# SENSOR_GARIS.net
KiCad netlist of a schematic drawn in EAGLE
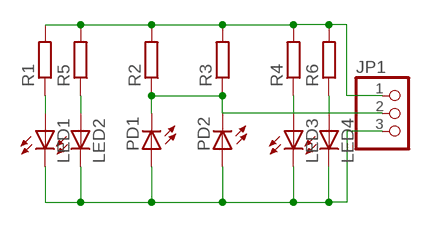
[diagram p0: schematic, sheet 1]

(export (version "E")
  (design (tool "Eeschema 10.0.6"))
  (components
    (comp (ref "JP1")
      (value "PINHD-1X3")
      (footprint "eagle-import:1X03")
      (libsource (lib "eagle-import") (part "PINHD-1X3"))
    )
    (comp (ref "LED1")
      (value "LED3MM")
      (footprint "eagle-import:LED3MM")
      (libsource (lib "eagle-import") (part "LED3MM"))
    )
    (comp (ref "LED2")
      (value "LED3MM")
      (footprint "eagle-import:LED3MM")
      (libsource (lib "eagle-import") (part "LED3MM"))
    )
    (comp (ref "LED3")
      (value "LED3MM")
      (footprint "eagle-import:LED3MM")
      (libsource (lib "eagle-import") (part "LED3MM"))
    )
    (comp (ref "LED4")
      (value "LED3MM")
      (footprint "eagle-import:LED3MM")
      (libsource (lib "eagle-import") (part "LED3MM"))
    )
    (comp (ref "PD1")
      (value "LED3MM")
      (footprint "eagle-import:LED3MM")
      (libsource (lib "eagle-import") (part "LED3MM"))
    )
    (comp (ref "PD2")
      (value "LED3MM")
      (footprint "eagle-import:LED3MM")
      (libsource (lib "eagle-import") (part "LED3MM"))
    )
    (comp (ref "R1")
      (value "R-EU_M0805")
      (footprint "eagle-import:M0805")
      (libsource (lib "eagle-import") (part "R-EU_M0805"))
    )
    (comp (ref "R2")
      (value "R-EU_M0805")
      (footprint "eagle-import:M0805")
      (libsource (lib "eagle-import") (part "R-EU_M0805"))
    )
    (comp (ref "R3")
      (value "R-EU_M0805")
      (footprint "eagle-import:M0805")
      (libsource (lib "eagle-import") (part "R-EU_M0805"))
    )
    (comp (ref "R4")
      (value "R-EU_M0805")
      (footprint "eagle-import:M0805")
      (libsource (lib "eagle-import") (part "R-EU_M0805"))
    )
    (comp (ref "R5")
      (value "R-EU_M0805")
      (footprint "eagle-import:M0805")
      (libsource (lib "eagle-import") (part "R-EU_M0805"))
    )
    (comp (ref "R6")
      (value "R-EU_M0805")
      (footprint "eagle-import:M0805")
      (libsource (lib "eagle-import") (part "R-EU_M0805"))
    )
  )
  (nets
    (net (code "1") (name "Net-(JP1-Pad1)") (class "Default")
      (node (ref "JP1") (pin "1") (pinfunction "1_1") (pintype "passive"))
      (node (ref "R1") (pin "2") (pinfunction "2_2") (pintype "passive"))
      (node (ref "R2") (pin "2") (pinfunction "2_2") (pintype "passive"))
      (node (ref "R3") (pin "2") (pinfunction "2_2") (pintype "passive"))
      (node (ref "R4") (pin "2") (pinfunction "2_2") (pintype "passive"))
      (node (ref "R5") (pin "2") (pinfunction "2_2") (pintype "passive"))
      (node (ref "R6") (pin "2") (pinfunction "2_2") (pintype "passive"))
    )
    (net (code "2") (name "Net-(LED1-C)") (class "Default")
      (node (ref "JP1") (pin "3") (pinfunction "3_3") (pintype "passive"))
      (node (ref "LED1") (pin "K") (pinfunction "C_K") (pintype "passive"))
      (node (ref "LED2") (pin "K") (pinfunction "C_K") (pintype "passive"))
      (node (ref "LED3") (pin "K") (pinfunction "C_K") (pintype "passive"))
      (node (ref "LED4") (pin "K") (pinfunction "C_K") (pintype "passive"))
      (node (ref "PD1") (pin "A") (pinfunction "A_A") (pintype "passive"))
      (node (ref "PD2") (pin "A") (pinfunction "A_A") (pintype "passive"))
    )
    (net (code "3") (name "Net-(LED1-PadA)") (class "Default")
      (node (ref "LED1") (pin "A") (pinfunction "A_A") (pintype "passive"))
      (node (ref "R1") (pin "1") (pinfunction "1_1") (pintype "passive"))
    )
    (net (code "4") (name "Net-(LED2-PadA)") (class "Default")
      (node (ref "LED2") (pin "A") (pinfunction "A_A") (pintype "passive"))
      (node (ref "R5") (pin "1") (pinfunction "1_1") (pintype "passive"))
    )
    (net (code "5") (name "Net-(LED3-PadA)") (class "Default")
      (node (ref "LED3") (pin "A") (pinfunction "A_A") (pintype "passive"))
      (node (ref "R4") (pin "1") (pinfunction "1_1") (pintype "passive"))
    )
    (net (code "6") (name "Net-(LED4-PadA)") (class "Default")
      (node (ref "LED4") (pin "A") (pinfunction "A_A") (pintype "passive"))
      (node (ref "R6") (pin "1") (pinfunction "1_1") (pintype "passive"))
    )
    (net (code "7") (name "Net-(PD1-C)") (class "Default")
      (node (ref "JP1") (pin "2") (pinfunction "2_2") (pintype "passive"))
      (node (ref "PD1") (pin "K") (pinfunction "C_K") (pintype "passive"))
      (node (ref "PD2") (pin "K") (pinfunction "C_K") (pintype "passive"))
      (node (ref "R2") (pin "1") (pinfunction "1_1") (pintype "passive"))
      (node (ref "R3") (pin "1") (pinfunction "1_1") (pintype "passive"))
    )
  )
)
